# control_board_schematic.net
KiCad netlist of a schematic drawn in EasyEDA
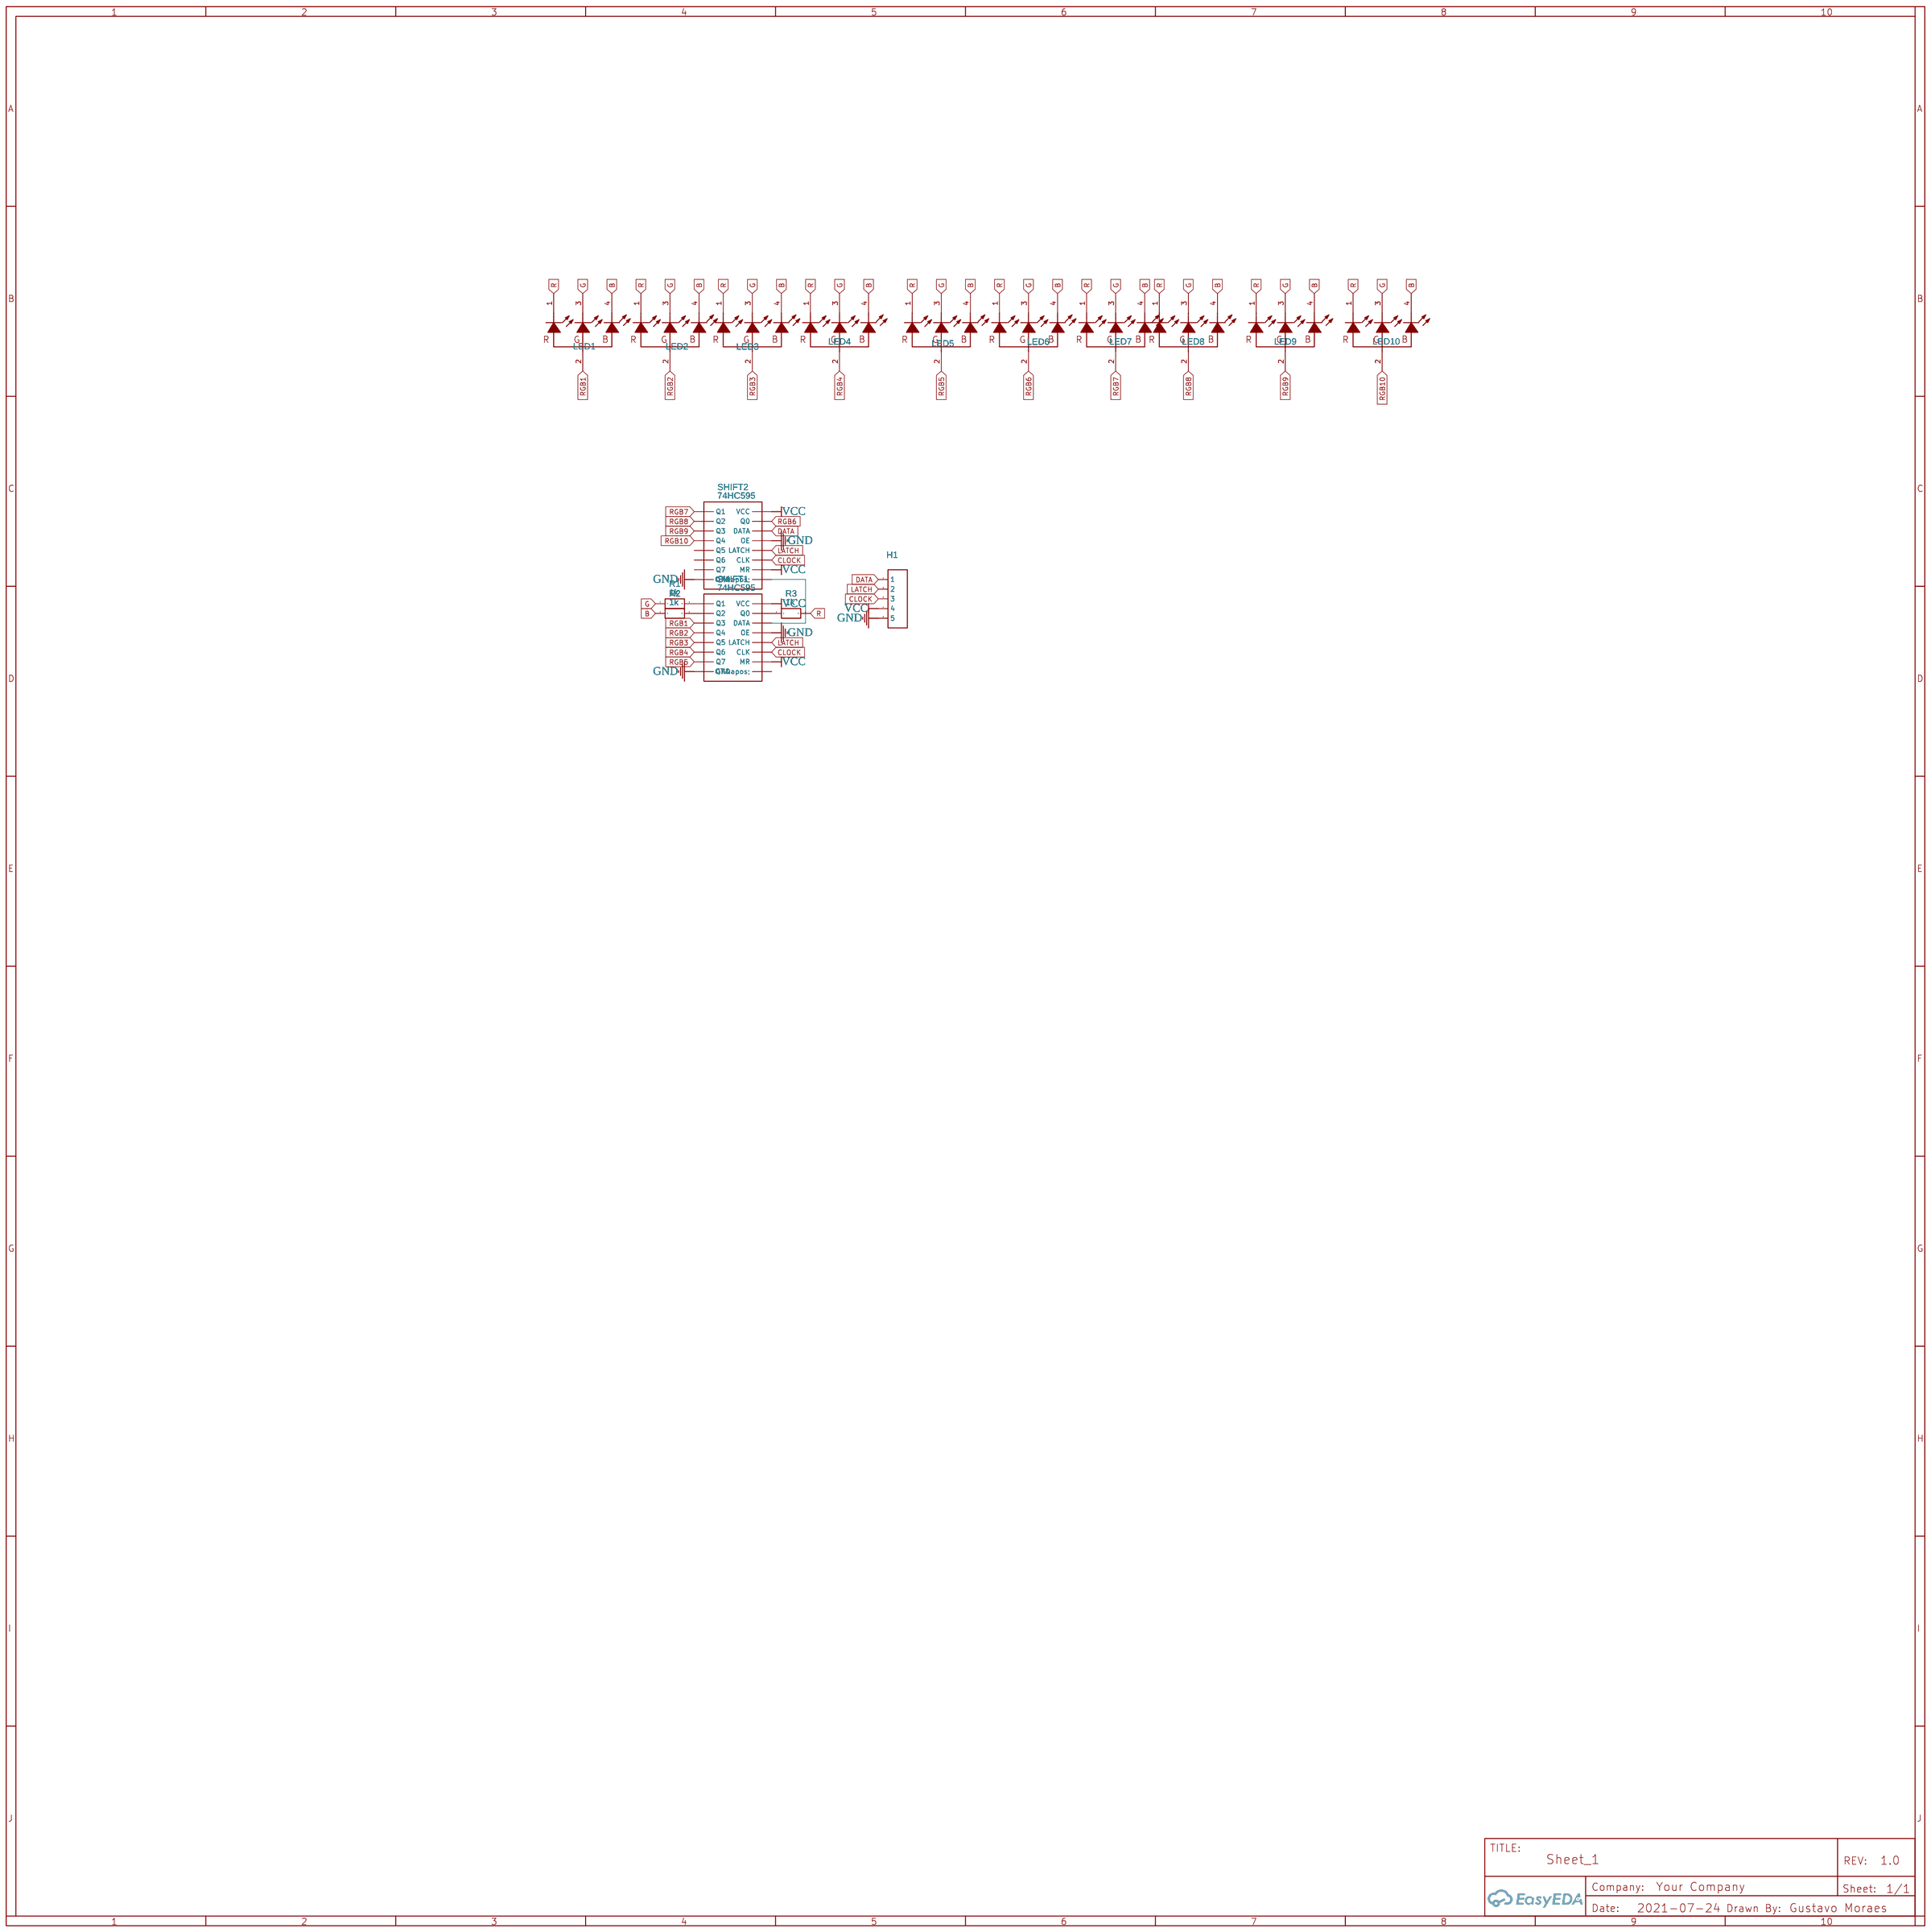
[diagram p0: schematic sheet]

(export (version "E")
  (design (tool "Eeschema 10.0.6"))
  (components
    (comp (ref "H1")
      (value "HDR-F-2.54_1x5")
      (fields (field (name "BOM_Supplier Part") "C50950"))
      (libsource (lib "") (part "HDR-F-2.54_1x5"))
    )
    (comp (ref "LED1")
      (value "φ5 RGB Transparent")
      (fields
        (field (name "BOM_Manufacturer Part") "φ5 RGB Transparent LED")
        (field (name "BOM_Supplier Part") "C32985")
      )
      (libsource (lib "") (part "φ5 RGB Transparent"))
    )
    (comp (ref "LED2")
      (value "φ5 RGB Transparent")
      (fields
        (field (name "BOM_Manufacturer Part") "φ5 RGB Transparent LED")
        (field (name "BOM_Supplier Part") "C32985")
      )
      (libsource (lib "") (part "φ5 RGB Transparent"))
    )
    (comp (ref "LED3")
      (value "φ5 RGB Transparent")
      (fields
        (field (name "BOM_Manufacturer Part") "φ5 RGB Transparent LED")
        (field (name "BOM_Supplier Part") "C32985")
      )
      (libsource (lib "") (part "φ5 RGB Transparent"))
    )
    (comp (ref "LED4")
      (value "φ5 RGB Transparent")
      (fields
        (field (name "BOM_Manufacturer Part") "φ5 RGB Transparent LED")
        (field (name "BOM_Supplier Part") "C32985")
      )
      (libsource (lib "") (part "φ5 RGB Transparent_1"))
    )
    (comp (ref "LED5")
      (value "φ5 RGB Transparent")
      (fields
        (field (name "BOM_Manufacturer Part") "φ5 RGB Transparent LED")
        (field (name "BOM_Supplier Part") "C32985")
      )
      (libsource (lib "") (part "φ5 RGB Transparent"))
    )
    (comp (ref "LED6")
      (value "φ5 RGB Transparent")
      (fields
        (field (name "BOM_Manufacturer Part") "φ5 RGB Transparent LED")
        (field (name "BOM_Supplier Part") "C32985")
      )
      (libsource (lib "") (part "φ5 RGB Transparent"))
    )
    (comp (ref "LED7")
      (value "φ5 RGB Transparent")
      (fields
        (field (name "BOM_Manufacturer Part") "φ5 RGB Transparent LED")
        (field (name "BOM_Supplier Part") "C32985")
      )
      (libsource (lib "") (part "φ5 RGB Transparent"))
    )
    (comp (ref "LED8")
      (value "φ5 RGB Transparent")
      (fields
        (field (name "BOM_Manufacturer Part") "φ5 RGB Transparent LED")
        (field (name "BOM_Supplier Part") "C32985")
      )
      (libsource (lib "") (part "φ5 RGB Transparent"))
    )
    (comp (ref "LED9")
      (value "φ5 RGB Transparent")
      (fields
        (field (name "BOM_Manufacturer Part") "φ5 RGB Transparent LED")
        (field (name "BOM_Supplier Part") "C32985")
      )
      (libsource (lib "") (part "φ5 RGB Transparent"))
    )
    (comp (ref "LED10")
      (value "φ5 RGB Transparent")
      (fields
        (field (name "BOM_Manufacturer Part") "φ5 RGB Transparent LED")
        (field (name "BOM_Supplier Part") "C32985")
      )
      (libsource (lib "") (part "φ5 RGB Transparent"))
    )
    (comp (ref "R1") (value "1k") (libsource (lib "") (part "R_AXIAL-0.3_EU")))
    (comp (ref "R2") (value "1k") (libsource (lib "") (part "R_AXIAL-0.3_EU")))
    (comp (ref "R3") (value "1k") (libsource (lib "") (part "R_AXIAL-0.3_EU")))
    (comp (ref "SHIFT1") (value "74HC595") (libsource (lib "") (part "74HC595")))
    (comp (ref "SHIFT2") (value "74HC595") (libsource (lib "") (part "74HC595")))
  )
  (nets
    (net (code "1") (name "B") (class "Default")
      (node (ref "LED1") (pin "4") (pinfunction "KB_4") (pintype "unspecified"))
      (node (ref "LED10") (pin "4") (pinfunction "KB_4") (pintype "unspecified"))
      (node (ref "LED2") (pin "4") (pinfunction "KB_4") (pintype "unspecified"))
      (node (ref "LED3") (pin "4") (pinfunction "KB_4") (pintype "unspecified"))
      (node (ref "LED4") (pin "4") (pinfunction "KB_4") (pintype "unspecified"))
      (node (ref "LED5") (pin "4") (pinfunction "KB_4") (pintype "unspecified"))
      (node (ref "LED6") (pin "4") (pinfunction "KB_4") (pintype "unspecified"))
      (node (ref "LED7") (pin "4") (pinfunction "KB_4") (pintype "unspecified"))
      (node (ref "LED8") (pin "4") (pinfunction "KB_4") (pintype "unspecified"))
      (node (ref "LED9") (pin "4") (pinfunction "KB_4") (pintype "unspecified"))
      (node (ref "R2") (pin "1") (pinfunction "1_1") (pintype "unspecified"))
    )
    (net (code "2") (name "CLOCK") (class "Default")
      (node (ref "H1") (pin "3") (pinfunction "3_3") (pintype "unspecified"))
      (node (ref "SHIFT1") (pin "11") (pinfunction "CLK_11") (pintype "unspecified"))
      (node (ref "SHIFT2") (pin "11") (pinfunction "CLK_11") (pintype "unspecified"))
    )
    (net (code "3") (name "DATA") (class "Default")
      (node (ref "H1") (pin "1") (pinfunction "1_1") (pintype "unspecified"))
      (node (ref "SHIFT2") (pin "14") (pinfunction "DATA_14") (pintype "unspecified"))
    )
    (net (code "4") (name "G") (class "Default")
      (node (ref "LED1") (pin "3") (pinfunction "KG_3") (pintype "unspecified"))
      (node (ref "LED10") (pin "3") (pinfunction "KG_3") (pintype "unspecified"))
      (node (ref "LED2") (pin "3") (pinfunction "KG_3") (pintype "unspecified"))
      (node (ref "LED3") (pin "3") (pinfunction "KG_3") (pintype "unspecified"))
      (node (ref "LED4") (pin "3") (pinfunction "KG_3") (pintype "unspecified"))
      (node (ref "LED5") (pin "3") (pinfunction "KG_3") (pintype "unspecified"))
      (node (ref "LED6") (pin "3") (pinfunction "KG_3") (pintype "unspecified"))
      (node (ref "LED7") (pin "3") (pinfunction "KG_3") (pintype "unspecified"))
      (node (ref "LED8") (pin "3") (pinfunction "KG_3") (pintype "unspecified"))
      (node (ref "LED9") (pin "3") (pinfunction "KG_3") (pintype "unspecified"))
      (node (ref "R1") (pin "1") (pinfunction "1_1") (pintype "unspecified"))
    )
    (net (code "5") (name "GND") (class "Default")
      (node (ref "H1") (pin "5") (pinfunction "5_5") (pintype "unspecified"))
      (node (ref "SHIFT1") (pin "13") (pinfunction "OE_13") (pintype "unspecified"))
      (node (ref "SHIFT1") (pin "8") (pinfunction "GND_8") (pintype "unspecified"))
      (node (ref "SHIFT2") (pin "13") (pinfunction "OE_13") (pintype "unspecified"))
      (node (ref "SHIFT2") (pin "8") (pinfunction "GND_8") (pintype "unspecified"))
    )
    (net (code "6") (name "LATCH") (class "Default")
      (node (ref "H1") (pin "2") (pinfunction "2_2") (pintype "unspecified"))
      (node (ref "SHIFT1") (pin "12") (pinfunction "LATCH_12") (pintype "unspecified"))
      (node (ref "SHIFT2") (pin "12") (pinfunction "LATCH_12") (pintype "unspecified"))
    )
    (net (code "7") (name "Net-(SHIFT1-DATA)") (class "Default")
      (node (ref "SHIFT1") (pin "14") (pinfunction "DATA_14") (pintype "unspecified"))
      (node (ref "SHIFT2") (pin "9") (pinfunction "Q7&apos;_9") (pintype "unspecified"))
    )
    (net (code "8") (name "Net-(SHIFT1-Q0)") (class "Default")
      (node (ref "R3") (pin "1") (pinfunction "1_1") (pintype "unspecified"))
      (node (ref "SHIFT1") (pin "15") (pinfunction "Q0_15") (pintype "unspecified"))
    )
    (net (code "9") (name "Net-(SHIFT1-Q1)") (class "Default")
      (node (ref "R1") (pin "2") (pinfunction "2_2") (pintype "unspecified"))
      (node (ref "SHIFT1") (pin "1") (pinfunction "Q1_1") (pintype "unspecified"))
    )
    (net (code "10") (name "Net-(SHIFT1-Q2)") (class "Default")
      (node (ref "R2") (pin "2") (pinfunction "2_2") (pintype "unspecified"))
      (node (ref "SHIFT1") (pin "2") (pinfunction "Q2_2") (pintype "unspecified"))
    )
    (net (code "11") (name "R") (class "Default")
      (node (ref "LED1") (pin "1") (pinfunction "KR_1") (pintype "unspecified"))
      (node (ref "LED10") (pin "1") (pinfunction "KR_1") (pintype "unspecified"))
      (node (ref "LED2") (pin "1") (pinfunction "KR_1") (pintype "unspecified"))
      (node (ref "LED3") (pin "1") (pinfunction "KR_1") (pintype "unspecified"))
      (node (ref "LED4") (pin "1") (pinfunction "KR_1") (pintype "unspecified"))
      (node (ref "LED5") (pin "1") (pinfunction "KR_1") (pintype "unspecified"))
      (node (ref "LED6") (pin "1") (pinfunction "KR_1") (pintype "unspecified"))
      (node (ref "LED7") (pin "1") (pinfunction "KR_1") (pintype "unspecified"))
      (node (ref "LED8") (pin "1") (pinfunction "KR_1") (pintype "unspecified"))
      (node (ref "LED9") (pin "1") (pinfunction "KR_1") (pintype "unspecified"))
      (node (ref "R3") (pin "2") (pinfunction "2_2") (pintype "unspecified"))
    )
    (net (code "12") (name "RGB1") (class "Default")
      (node (ref "LED1") (pin "2") (pinfunction "CA_2") (pintype "unspecified"))
      (node (ref "SHIFT1") (pin "3") (pinfunction "Q3_3") (pintype "unspecified"))
    )
    (net (code "13") (name "RGB2") (class "Default")
      (node (ref "LED2") (pin "2") (pinfunction "CA_2") (pintype "unspecified"))
      (node (ref "SHIFT1") (pin "4") (pinfunction "Q4_4") (pintype "unspecified"))
    )
    (net (code "14") (name "RGB3") (class "Default")
      (node (ref "LED3") (pin "2") (pinfunction "CA_2") (pintype "unspecified"))
      (node (ref "SHIFT1") (pin "5") (pinfunction "Q5_5") (pintype "unspecified"))
    )
    (net (code "15") (name "RGB4") (class "Default")
      (node (ref "LED4") (pin "2") (pinfunction "CA_2") (pintype "unspecified"))
      (node (ref "SHIFT1") (pin "6") (pinfunction "Q6_6") (pintype "unspecified"))
    )
    (net (code "16") (name "RGB5") (class "Default")
      (node (ref "LED5") (pin "2") (pinfunction "CA_2") (pintype "unspecified"))
      (node (ref "SHIFT1") (pin "7") (pinfunction "Q7_7") (pintype "unspecified"))
    )
    (net (code "17") (name "RGB6") (class "Default")
      (node (ref "LED6") (pin "2") (pinfunction "CA_2") (pintype "unspecified"))
      (node (ref "SHIFT2") (pin "15") (pinfunction "Q0_15") (pintype "unspecified"))
    )
    (net (code "18") (name "RGB7") (class "Default")
      (node (ref "LED7") (pin "2") (pinfunction "CA_2") (pintype "unspecified"))
      (node (ref "SHIFT2") (pin "1") (pinfunction "Q1_1") (pintype "unspecified"))
    )
    (net (code "19") (name "RGB8") (class "Default")
      (node (ref "LED8") (pin "2") (pinfunction "CA_2") (pintype "unspecified"))
      (node (ref "SHIFT2") (pin "2") (pinfunction "Q2_2") (pintype "unspecified"))
    )
    (net (code "20") (name "RGB9") (class "Default")
      (node (ref "LED9") (pin "2") (pinfunction "CA_2") (pintype "unspecified"))
      (node (ref "SHIFT2") (pin "3") (pinfunction "Q3_3") (pintype "unspecified"))
    )
    (net (code "21") (name "RGB10") (class "Default")
      (node (ref "LED10") (pin "2") (pinfunction "CA_2") (pintype "unspecified"))
      (node (ref "SHIFT2") (pin "4") (pinfunction "Q4_4") (pintype "unspecified"))
    )
    (net (code "22") (name "VCC") (class "Default")
      (node (ref "H1") (pin "4") (pinfunction "4_4") (pintype "unspecified"))
      (node (ref "SHIFT1") (pin "10") (pinfunction "MR_10") (pintype "unspecified"))
      (node (ref "SHIFT1") (pin "16") (pinfunction "VCC_16") (pintype "unspecified"))
      (node (ref "SHIFT2") (pin "10") (pinfunction "MR_10") (pintype "unspecified"))
      (node (ref "SHIFT2") (pin "16") (pinfunction "VCC_16") (pintype "unspecified"))
    )
    (net (code "23") (name "unconnected-(SHIFT1-Q7&apos;-Pad9)") (class "Default")
      (node (ref "SHIFT1") (pin "9") (pinfunction "Q7&apos;_9") (pintype "unspecified"))
    )
    (net (code "24") (name "unconnected-(SHIFT2-Q5-Pad5)") (class "Default")
      (node (ref "SHIFT2") (pin "5") (pinfunction "Q5_5") (pintype "unspecified"))
    )
    (net (code "25") (name "unconnected-(SHIFT2-Q6-Pad6)") (class "Default")
      (node (ref "SHIFT2") (pin "6") (pinfunction "Q6_6") (pintype "unspecified"))
    )
    (net (code "26") (name "unconnected-(SHIFT2-Q7-Pad7)") (class "Default")
      (node (ref "SHIFT2") (pin "7") (pinfunction "Q7_7") (pintype "unspecified"))
    )
  )
)
